# Task_with_ESP32.net
KiCad netlist of a schematic drawn in Altium Designer
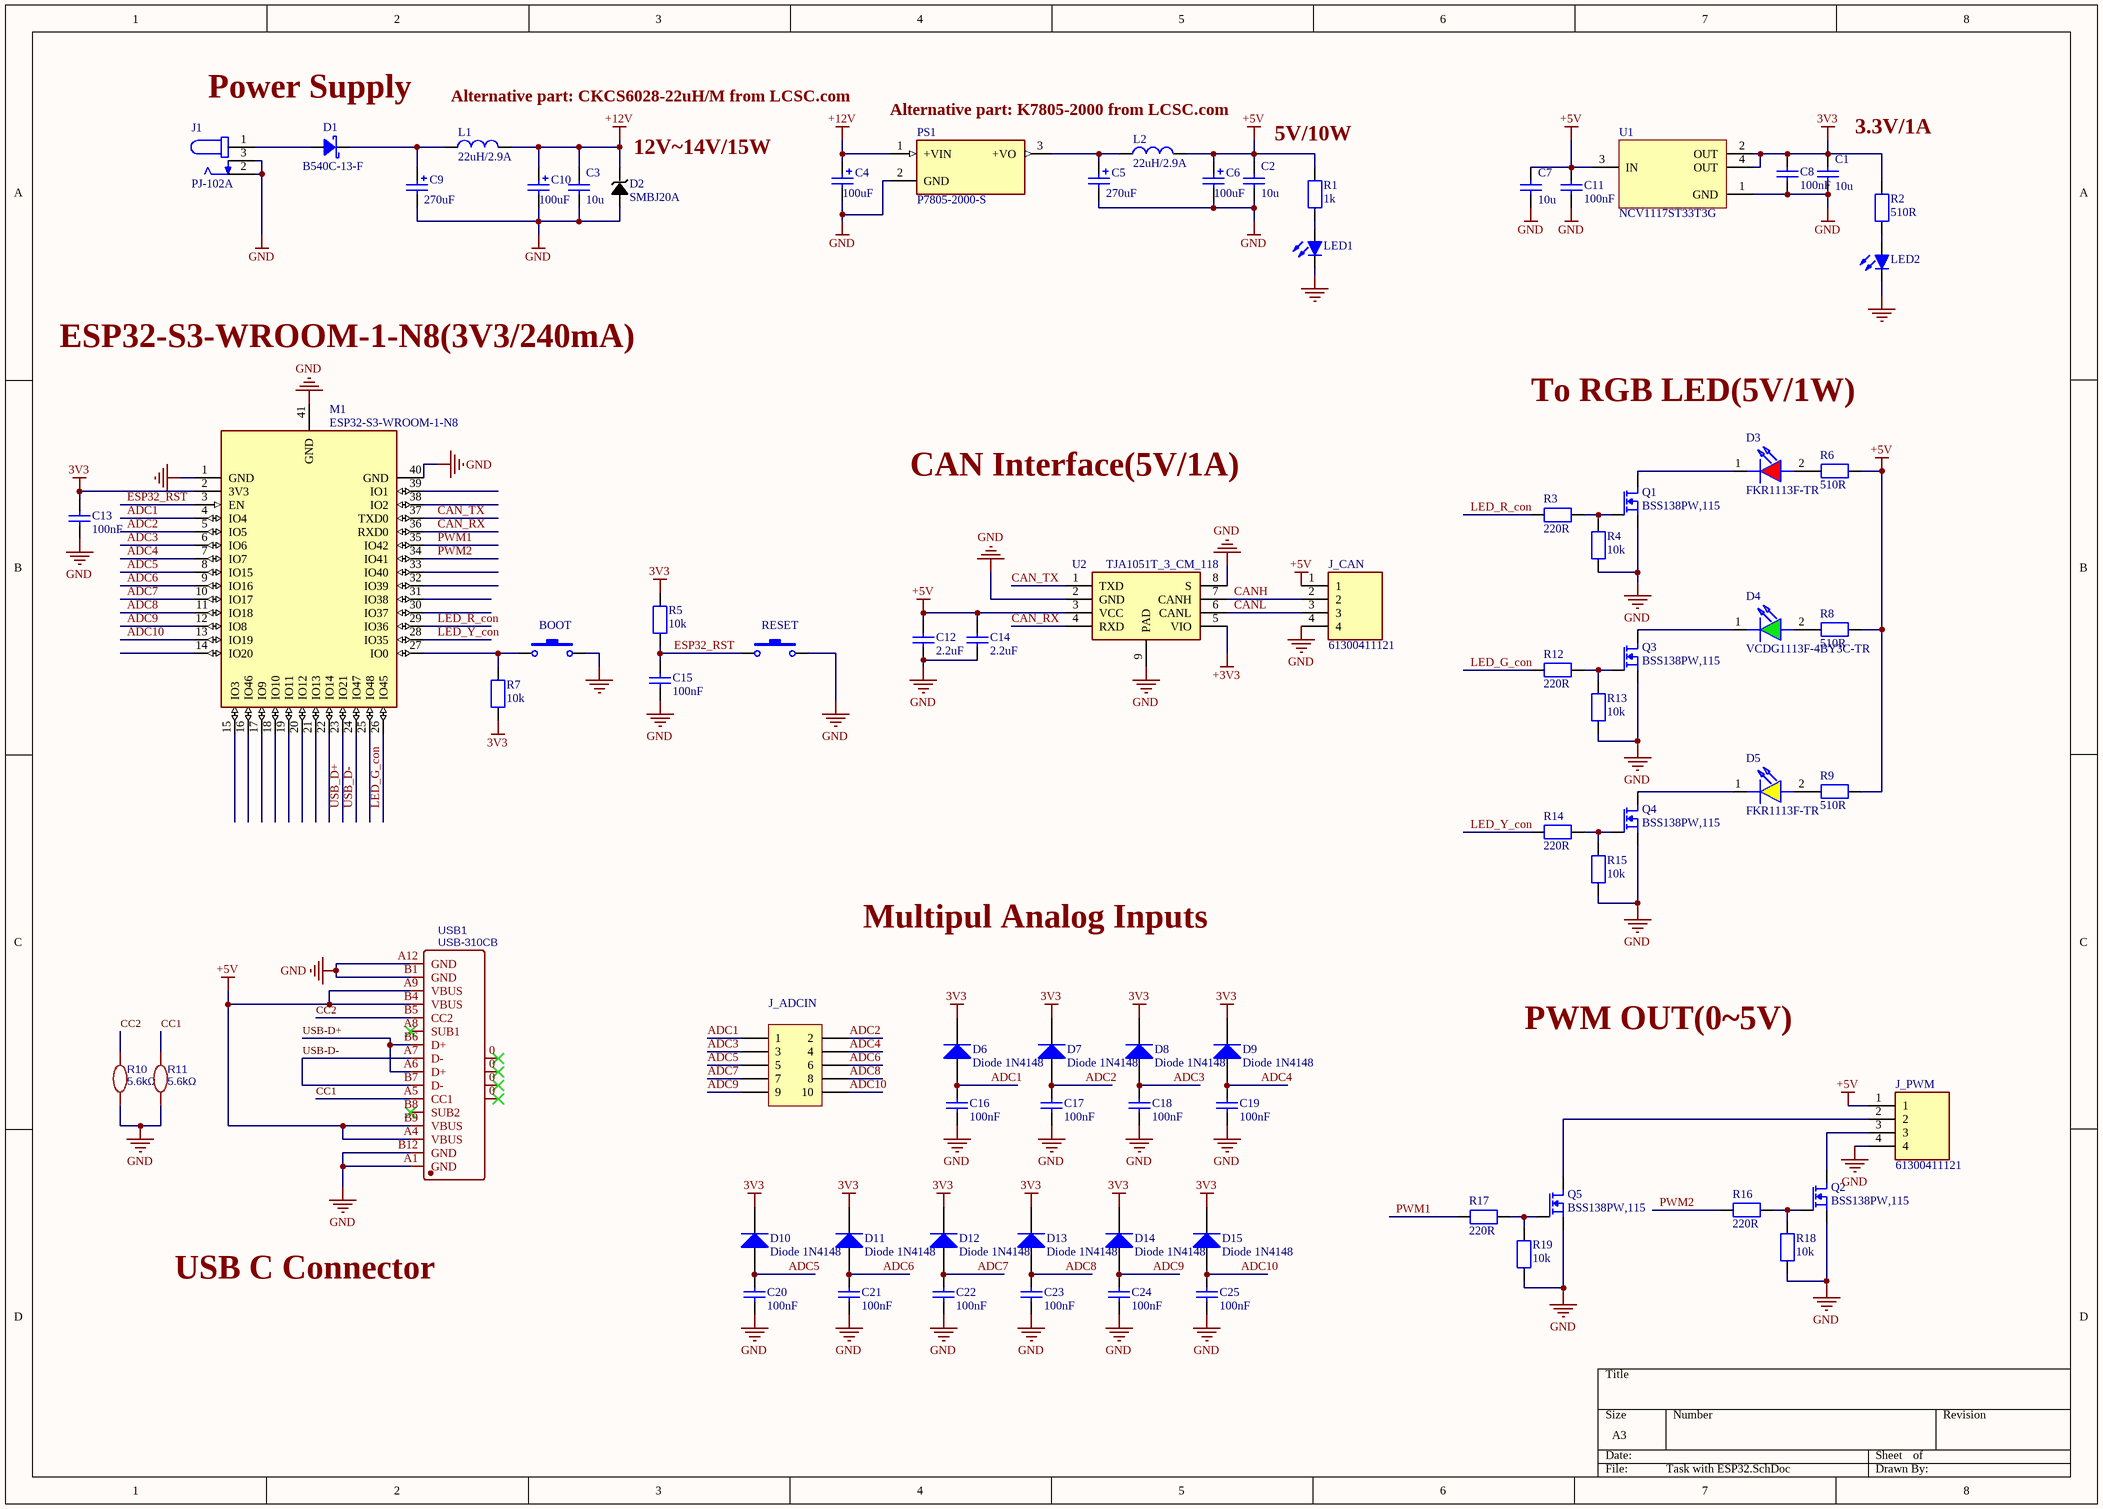
[diagram p0: Task with ESP32.SchDoc]

(export (version "E")
  (design (tool "Eeschema 10.0.6"))
  (components
    (comp (ref "BOOT")
      (value "TL3305BF260QG")
      (footprint "SW_TL3305BF260QG")
      (description "SWITCH TACTILE SPST-NO 0.05A 12V")
      (fields (field (name "MANUFACTURER") "E-Switch"))
      (libsource (lib "Humidity Regulator") (part "TL3305BF260QG"))
    )
    (comp (ref "C1")
      (value "10u")
      (footprint "C1206")
      (description "10uF ± 10% 25V")
      (fields
        (field (name "MANUFACTURER") "Yageo")
        (field (name "MANUFACTURER PART NUMBER") "CC1206KKX7R8BB106")
      )
      (libsource (lib "Humidity Regulator") (part "10uF ± 10% 25V"))
    )
    (comp (ref "C2")
      (value "10u")
      (footprint "C1206")
      (description "10uF ± 10% 25V")
      (fields
        (field (name "MANUFACTURER") "Yageo")
        (field (name "MANUFACTURER PART NUMBER") "CC1206KKX7R8BB106")
      )
      (libsource (lib "Humidity Regulator") (part "10uF ± 10% 25V"))
    )
    (comp (ref "C3")
      (value "10u")
      (footprint "C1206")
      (description "10uF ± 10% 25V")
      (fields
        (field (name "MANUFACTURER") "Yageo")
        (field (name "MANUFACTURER PART NUMBER") "CC1206KKX7R8BB106")
      )
      (libsource (lib "Humidity Regulator") (part "10uF ± 10% 25V"))
    )
    (comp (ref "C4")
      (value "100uF")
      (footprint "CAP_EEUFC1E101S")
      (description "CAP ALUM 100UF 20% 25V SMD")
      (fields
        (field (name "MANUFACTURER PART NUMBER") "EEU-FC1E101S")
        (field (name "MANUFACTURER") "Panasonic")
      )
      (libsource (lib "Humidity Regulator") (part "EEU-FC1E101S"))
    )
    (comp (ref "C5")
      (value "270uF")
      (footprint "CAP_EEU-FK1E271B")
      (description "CAP ALUM 270UF 20% 25V SMD")
      (fields
        (field (name "MANUFACTURER PART NUMBER") "EEU-FC1E271B")
        (field (name "MANUFACTURER") "Panasonic")
      )
      (libsource (lib "Humidity Regulator") (part "EEU-FC1E271B"))
    )
    (comp (ref "C6")
      (value "100uF")
      (footprint "CAP_EEUFC1E101S")
      (description "CAP ALUM 100UF 20% 25V SMD")
      (fields
        (field (name "MANUFACTURER PART NUMBER") "EEU-FC1E101S")
        (field (name "MANUFACTURER") "Panasonic")
      )
      (libsource (lib "Humidity Regulator") (part "EEU-FC1E101S"))
    )
    (comp (ref "C7")
      (value "10u")
      (footprint "C1206")
      (description "10uF ± 10% 25V")
      (fields
        (field (name "MANUFACTURER") "Yageo")
        (field (name "MANUFACTURER PART NUMBER") "CC1206KKX7R8BB106")
      )
      (libsource (lib "Humidity Regulator") (part "10uF ± 10% 25V"))
    )
    (comp (ref "C8")
      (value "100nF")
      (footprint "C0603")
      (description "100nF ± 10% 50V")
      (fields
        (field (name "MANUFACTURER") "Yageo")
        (field (name "MANUFACTURER PART NUMBER") "CC0603KRX7R9BB104")
      )
      (libsource (lib "Humidity Regulator") (part "100nF ± 10% 50V"))
    )
    (comp (ref "C9")
      (value "270uF")
      (footprint "CAP_EEU-FK1E271B")
      (description "CAP ALUM 270UF 20% 25V SMD")
      (fields
        (field (name "MANUFACTURER PART NUMBER") "EEU-FC1E271B")
        (field (name "MANUFACTURER") "Panasonic")
      )
      (libsource (lib "Humidity Regulator") (part "EEU-FC1E271B"))
    )
    (comp (ref "C10")
      (value "100uF")
      (footprint "CAP_EEUFC1E101S")
      (description "CAP ALUM 100UF 20% 25V SMD")
      (fields
        (field (name "MANUFACTURER PART NUMBER") "EEU-FC1E101S")
        (field (name "MANUFACTURER") "Panasonic")
      )
      (libsource (lib "Humidity Regulator") (part "EEU-FC1E101S"))
    )
    (comp (ref "C11")
      (value "100nF")
      (footprint "C0603")
      (description "100nF ± 10% 50V")
      (fields
        (field (name "MANUFACTURER") "Yageo")
        (field (name "MANUFACTURER PART NUMBER") "CC0603KRX7R9BB104")
      )
      (libsource (lib "Humidity Regulator") (part "100nF ± 10% 50V"))
    )
    (comp (ref "C12")
      (value "2.2uF")
      (footprint "C0603")
      (description "2.2uF ± 10% 50V")
      (fields
        (field (name "MANUFACTURER") "Yageo")
        (field (name "MANUFACTURER PART NUMBER") "GRM188R61H225ME11J")
      )
      (libsource (lib "VESC_MotorController") (part "2.2uF ± 10% 50V"))
    )
    (comp (ref "C13")
      (value "100nF")
      (footprint "C0603")
      (description "100nF ± 10% 50V")
      (fields
        (field (name "MANUFACTURER") "Yageo")
        (field (name "MANUFACTURER PART NUMBER") "CC0603KRX7R9BB104")
      )
      (libsource (lib "Humidity Regulator") (part "100nF ± 10% 50V"))
    )
    (comp (ref "C14")
      (value "2.2uF")
      (footprint "C0603")
      (description "2.2uF ± 10% 50V")
      (fields
        (field (name "MANUFACTURER") "Yageo")
        (field (name "MANUFACTURER PART NUMBER") "GRM188R61H225ME11J")
      )
      (libsource (lib "VESC_MotorController") (part "2.2uF ± 10% 50V"))
    )
    (comp (ref "C15")
      (value "100nF")
      (footprint "C0603")
      (description "100nF ± 10% 50V")
      (fields
        (field (name "MANUFACTURER") "Yageo")
        (field (name "MANUFACTURER PART NUMBER") "CC0603KRX7R9BB104")
      )
      (libsource (lib "Humidity Regulator") (part "100nF ± 10% 50V"))
    )
    (comp (ref "C16")
      (value "100nF")
      (footprint "C0402")
      (description "100nF ± 10% 50V")
      (fields
        (field (name "MANUFACTURER") "Yageo")
        (field (name "MANUFACTURER PART NUMBER") "CS0603KRX7R9BB104")
      )
      (libsource (lib "Task with ESP32") (part "100nF ± 10% 50V"))
    )
    (comp (ref "C17")
      (value "100nF")
      (footprint "C0402")
      (description "100nF ± 10% 50V")
      (fields
        (field (name "MANUFACTURER") "Yageo")
        (field (name "MANUFACTURER PART NUMBER") "CS0603KRX7R9BB104")
      )
      (libsource (lib "Task with ESP32") (part "100nF ± 10% 50V"))
    )
    (comp (ref "C18")
      (value "100nF")
      (footprint "C0402")
      (description "100nF ± 10% 50V")
      (fields
        (field (name "MANUFACTURER") "Yageo")
        (field (name "MANUFACTURER PART NUMBER") "CS0603KRX7R9BB104")
      )
      (libsource (lib "Task with ESP32") (part "100nF ± 10% 50V"))
    )
    (comp (ref "C19")
      (value "100nF")
      (footprint "C0402")
      (description "100nF ± 10% 50V")
      (fields
        (field (name "MANUFACTURER") "Yageo")
        (field (name "MANUFACTURER PART NUMBER") "CS0603KRX7R9BB104")
      )
      (libsource (lib "Task with ESP32") (part "100nF ± 10% 50V"))
    )
    (comp (ref "C20")
      (value "100nF")
      (footprint "C0402")
      (description "100nF ± 10% 50V")
      (fields
        (field (name "MANUFACTURER") "Yageo")
        (field (name "MANUFACTURER PART NUMBER") "CS0603KRX7R9BB104")
      )
      (libsource (lib "Task with ESP32") (part "100nF ± 10% 50V"))
    )
    (comp (ref "C21")
      (value "100nF")
      (footprint "C0402")
      (description "100nF ± 10% 50V")
      (fields
        (field (name "MANUFACTURER") "Yageo")
        (field (name "MANUFACTURER PART NUMBER") "CS0603KRX7R9BB104")
      )
      (libsource (lib "Task with ESP32") (part "100nF ± 10% 50V"))
    )
    (comp (ref "C22")
      (value "100nF")
      (footprint "C0402")
      (description "100nF ± 10% 50V")
      (fields
        (field (name "MANUFACTURER") "Yageo")
        (field (name "MANUFACTURER PART NUMBER") "CS0603KRX7R9BB104")
      )
      (libsource (lib "Task with ESP32") (part "100nF ± 10% 50V"))
    )
    (comp (ref "C23")
      (value "100nF")
      (footprint "C0402")
      (description "100nF ± 10% 50V")
      (fields
        (field (name "MANUFACTURER") "Yageo")
        (field (name "MANUFACTURER PART NUMBER") "CS0603KRX7R9BB104")
      )
      (libsource (lib "Task with ESP32") (part "100nF ± 10% 50V"))
    )
    (comp (ref "C24")
      (value "100nF")
      (footprint "C0402")
      (description "100nF ± 10% 50V")
      (fields
        (field (name "MANUFACTURER") "Yageo")
        (field (name "MANUFACTURER PART NUMBER") "CS0603KRX7R9BB104")
      )
      (libsource (lib "Task with ESP32") (part "100nF ± 10% 50V"))
    )
    (comp (ref "C25")
      (value "100nF")
      (footprint "C0402")
      (description "100nF ± 10% 50V")
      (fields
        (field (name "MANUFACTURER") "Yageo")
        (field (name "MANUFACTURER PART NUMBER") "CS0603KRX7R9BB104")
      )
      (libsource (lib "Task with ESP32") (part "100nF ± 10% 50V"))
    )
    (comp (ref "D1")
      (value "B540C-13-F")
      (footprint "DO-214AB2")
      (description "Schottky Diodes & Rectifiers 40V 5A")
      (fields (field (name "MANUFACTURER") "Diodes"))
      (libsource (lib "Humidity Regulator") (part "B540C-13-F"))
    )
    (comp (ref "D2")
      (value "SMBJ20A")
      (footprint "DO-214AA2")
      (description "ESD Suppressors / TVS Diodes 600W, 23.4V, 5%, Unidirectional, TVS")
      (fields (field (name "MANUFACTURER") "Littelfuse"))
      (libsource (lib "Humidity Regulator") (part "ZM4746A-GS08"))
    )
    (comp (ref "D3")
      (value "FKR1113F-TR")
      (footprint "VCDG1113F4BY3CTR")
      (description "R/A LED")
      (fields (field (name "MANUFACTURER") "Stanley Electric"))
      (libsource (lib "Task with ESP32") (part "LED_RED"))
    )
    (comp (ref "D4")
      (value "VCDG1113F-4BY3C-TR")
      (footprint "VCDG1113F4BY3CTR")
      (description "R/A LED")
      (fields (field (name "MANUFACTURER") "Stanley Electric"))
      (libsource (lib "Task with ESP32") (part "LED_GREEN"))
    )
    (comp (ref "D5")
      (value "FKR1113F-TR")
      (footprint "VCDG1113F4BY3CTR")
      (description "R/A LED")
      (fields
        (field (name "MANUFACTURER") "Stanley Electric")
        (field (name "MANUFACTURER PART NUMBER") "FKY1113F-TR")
      )
      (libsource (lib "Task with ESP32") (part "LED_YELLOW"))
    )
    (comp (ref "D6")
      (value "Diode 1N4148")
      (footprint "DO-35")
      (description "High Conductance Fast Diode")
      (fields (field (name "PUBLISHER") "Altium Limited"))
      (libsource (lib "Miscellaneous Devices") (part "Diode 1N4148"))
    )
    (comp (ref "D7")
      (value "Diode 1N4148")
      (footprint "DO-35")
      (description "High Conductance Fast Diode")
      (fields (field (name "PUBLISHER") "Altium Limited"))
      (libsource (lib "Miscellaneous Devices") (part "Diode 1N4148"))
    )
    (comp (ref "D8")
      (value "Diode 1N4148")
      (footprint "DO-35")
      (description "High Conductance Fast Diode")
      (fields (field (name "PUBLISHER") "Altium Limited"))
      (libsource (lib "Miscellaneous Devices") (part "Diode 1N4148"))
    )
    (comp (ref "D9")
      (value "Diode 1N4148")
      (footprint "DO-35")
      (description "High Conductance Fast Diode")
      (fields (field (name "PUBLISHER") "Altium Limited"))
      (libsource (lib "Miscellaneous Devices") (part "Diode 1N4148"))
    )
    (comp (ref "D10")
      (value "Diode 1N4148")
      (footprint "DO-35")
      (description "High Conductance Fast Diode")
      (fields (field (name "PUBLISHER") "Altium Limited"))
      (libsource (lib "Miscellaneous Devices") (part "Diode 1N4148"))
    )
    (comp (ref "D11")
      (value "Diode 1N4148")
      (footprint "DO-35")
      (description "High Conductance Fast Diode")
      (fields (field (name "PUBLISHER") "Altium Limited"))
      (libsource (lib "Miscellaneous Devices") (part "Diode 1N4148"))
    )
    (comp (ref "D12")
      (value "Diode 1N4148")
      (footprint "DO-35")
      (description "High Conductance Fast Diode")
      (fields (field (name "PUBLISHER") "Altium Limited"))
      (libsource (lib "Miscellaneous Devices") (part "Diode 1N4148"))
    )
    (comp (ref "D13")
      (value "Diode 1N4148")
      (footprint "DO-35")
      (description "High Conductance Fast Diode")
      (fields (field (name "PUBLISHER") "Altium Limited"))
      (libsource (lib "Miscellaneous Devices") (part "Diode 1N4148"))
    )
    (comp (ref "D14")
      (value "Diode 1N4148")
      (footprint "DO-35")
      (description "High Conductance Fast Diode")
      (fields (field (name "PUBLISHER") "Altium Limited"))
      (libsource (lib "Miscellaneous Devices") (part "Diode 1N4148"))
    )
    (comp (ref "D15")
      (value "Diode 1N4148")
      (footprint "DO-35")
      (description "High Conductance Fast Diode")
      (fields (field (name "PUBLISHER") "Altium Limited"))
      (libsource (lib "Miscellaneous Devices") (part "Diode 1N4148"))
    )
    (comp (ref "J1")
      (value "PJ-102A")
      (footprint "CUI_PJ-102A")
      (description "CONN PWR JACK 2X5.5MM SOLDER")
      (fields (field (name "MANUFACTURER") "CUI Devices"))
      (libsource (lib "WirelessCharger") (part "PJ-102A"))
    )
    (comp (ref "J_ADCIN")
      (value "~")
      (footprint "HDR2X5H")
      (description "Header, 5-Pin, Dual row, Right Angle")
      (fields (field (name "PUBLISHER") "Altium Limited"))
      (libsource (lib "Miscellaneous Connectors") (part "Header 5X2H"))
    )
    (comp (ref "J_CAN")
      (value "61300411121")
      (footprint "61300411121")
      (description "Headers & Wire Housings WR-PHD 2.54mm Hdr 4P Single Str Gold")
      (fields (field (name "MANUFACTURER") "Wurth Electronic"))
      (libsource (lib "Task with ESP32") (part "Header 4 Pin"))
    )
    (comp (ref "J_PWM")
      (value "61300411121")
      (footprint "61300411121")
      (description "Headers & Wire Housings WR-PHD 2.54mm Hdr 4P Single Str Gold")
      (fields (field (name "MANUFACTURER") "Wurth Electronic"))
      (libsource (lib "Task with ESP32") (part "Header 4 Pin"))
    )
    (comp (ref "L1")
      (value "22uH/2.9A")
      (footprint "IND_SRP6030")
      (description "Power Inductors - SMD Ind,7.1x6.6x2.8mm,22uH+/-20%,2.9A,shd")
      (fields
        (field (name "MANUFACTURER PART NUMBER") "SRP6030WA-220M")
        (field (name "MANUFACTURER") "Bourns")
      )
      (libsource (lib "Humidity Regulator") (part "SRP6030WA-220M"))
    )
    (comp (ref "L2")
      (value "22uH/2.9A")
      (footprint "IND_SRP6030")
      (description "Power Inductors - SMD Ind,7.1x6.6x2.8mm,22uH+/-20%,2.9A,shd")
      (fields
        (field (name "MANUFACTURER PART NUMBER") "SRP6030WA-220M")
        (field (name "MANUFACTURER") "Bourns")
      )
      (libsource (lib "Humidity Regulator") (part "SRP6030WA-220M"))
    )
    (comp (ref "LED1")
      (value "SML-D12U1WT86")
      (footprint "LED0603")
      (description "Typical RED GaAs LED")
      (fields (field (name "MANUFACTURER") "Rohm Semiconductor"))
      (libsource (lib "Humidity Regulator") (part "SML-D12U1WT86"))
    )
    (comp (ref "LED2")
      (value "SML-D12U1WT86")
      (footprint "LED0603")
      (description "Typical RED GaAs LED")
      (fields (field (name "MANUFACTURER") "Rohm Semiconductor"))
      (libsource (lib "Humidity Regulator") (part "SML-D12U1WT86"))
    )
    (comp (ref "M1")
      (value "ESP32-S3-WROOM-1-N8")
      (footprint "ESP32-S3-WROOM-1-N8")
      (description "Bluetooth, WiFi 802.11b/g/n, Bluetooth v5.0 Transceiver Module 2.4GHz PCB Trace Surface Mount")
      (fields (field (name "MANUFACTURER") "Espressif Systems"))
      (libsource (lib "Humidity Regulator") (part "ESP32-S3-WROOM-1-N8"))
    )
    (comp (ref "PS1")
      (value "P7805-2000-S")
      (footprint "CONV_P7805-2000-S")
      (description "2 A Output Current, 6~36 Vdc Input, SIP, Non-Isolated, Dc-Dc Converter")
      (fields (field (name "MANUFACTURER") "CUI Inc."))
      (libsource (lib "P7805-2000-S") (part "P7805-2000-S"))
    )
    (comp (ref "Q1")
      (value "BSS138PW,115")
      (footprint "SOT323-3")
      (description "MOSFET, N CH, 60V, 0.2A")
      (fields (field (name "MANUFACTURER") "Nexperia"))
      (libsource (lib "Humidity Regulator") (part "BSS138PW,115"))
    )
    (comp (ref "Q2")
      (value "BSS138PW,115")
      (footprint "SOT323-3")
      (description "MOSFET, N CH, 60V, 0.2A")
      (fields (field (name "MANUFACTURER") "Nexperia"))
      (libsource (lib "Humidity Regulator") (part "BSS138PW,115"))
    )
    (comp (ref "Q3")
      (value "BSS138PW,115")
      (footprint "SOT323-3")
      (description "MOSFET, N CH, 60V, 0.2A")
      (fields (field (name "MANUFACTURER") "Nexperia"))
      (libsource (lib "Humidity Regulator") (part "BSS138PW,115"))
    )
    (comp (ref "Q4")
      (value "BSS138PW,115")
      (footprint "SOT323-3")
      (description "MOSFET, N CH, 60V, 0.2A")
      (fields (field (name "MANUFACTURER") "Nexperia"))
      (libsource (lib "Humidity Regulator") (part "BSS138PW,115"))
    )
    (comp (ref "Q5")
      (value "BSS138PW,115")
      (footprint "SOT323-3")
      (description "MOSFET, N CH, 60V, 0.2A")
      (fields (field (name "MANUFACTURER") "Nexperia"))
      (libsource (lib "Humidity Regulator") (part "BSS138PW,115"))
    )
    (comp (ref "R1")
      (value "1k")
      (footprint "R0603")
      (description "1 kOhms ±1% 0.1W")
      (fields
        (field (name "MANUFACTURER") "Yageo")
        (field (name "MANUFACTURER PART NUMBER") "RC0603FR-071KL")
      )
      (libsource (lib "Humidity Regulator") (part "1 kOhms ±1% 0.1W"))
    )
    (comp (ref "R2")
      (value "510R")
      (footprint "R0603")
      (description "510 Ohm ±1% 0.1W")
      (fields
        (field (name "MANUFACTURER") "Yageo")
        (field (name "MANUFACTURER PART NUMBER") "RC0603FR-07510RL")
      )
      (libsource (lib "Humidity Regulator") (part "510 Ohm ±1% 0.1W"))
    )
    (comp (ref "R3")
      (value "220R")
      (footprint "R0603")
      (description "220 Ohm ±1% 0.1W")
      (fields
        (field (name "MANUFACTURER") "Yageo")
        (field (name "MANUFACTURER PART NUMBER") "RC0603FR-07220RL")
      )
      (libsource (lib "Humidity Regulator") (part "220 Ohm ±1% 0.1W"))
    )
    (comp (ref "R4")
      (value "10k")
      (footprint "R0603")
      (description "10 kOhms ±1% 0.1W")
      (fields
        (field (name "MANUFACTURER") "Yageo")
        (field (name "MANUFACTURER PART NUMBER") "RC0603FR-0710KL")
      )
      (libsource (lib "Humidity Regulator") (part "10 kOhms ±1% 0.1W"))
    )
    (comp (ref "R5")
      (value "10k")
      (footprint "R0603")
      (description "10 kOhms ±1% 0.1W")
      (fields
        (field (name "MANUFACTURER") "Yageo")
        (field (name "MANUFACTURER PART NUMBER") "RC0603FR-0710KL")
      )
      (libsource (lib "Humidity Regulator") (part "10 kOhms ±1% 0.1W"))
    )
    (comp (ref "R6")
      (value "510R")
      (footprint "R0603")
      (description "510 Ohm ±1% 0.1W")
      (fields
        (field (name "MANUFACTURER") "Yageo")
        (field (name "MANUFACTURER PART NUMBER") "RC0603FR-07510RL")
      )
      (libsource (lib "Humidity Regulator") (part "510 Ohm ±1% 0.1W"))
    )
    (comp (ref "R7")
      (value "10k")
      (footprint "R0603")
      (description "10 kOhms ±1% 0.1W")
      (fields
        (field (name "MANUFACTURER") "Yageo")
        (field (name "MANUFACTURER PART NUMBER") "RC0603FR-0710KL")
      )
      (libsource (lib "Humidity Regulator") (part "10 kOhms ±1% 0.1W"))
    )
    (comp (ref "R8")
      (value "510R")
      (footprint "R0603")
      (description "510 Ohm ±1% 0.1W")
      (fields
        (field (name "MANUFACTURER") "Yageo")
        (field (name "MANUFACTURER PART NUMBER") "RC0603FR-07510RL")
      )
      (libsource (lib "Humidity Regulator") (part "510 Ohm ±1% 0.1W"))
    )
    (comp (ref "R9")
      (value "510R")
      (footprint "R0603")
      (description "510 Ohm ±1% 0.1W")
      (fields
        (field (name "MANUFACTURER") "Yageo")
        (field (name "MANUFACTURER PART NUMBER") "RC0603FR-07510RL")
      )
      (libsource (lib "Humidity Regulator") (part "510 Ohm ±1% 0.1W"))
    )
    (comp (ref "R10")
      (value "5.6kΩ")
      (footprint "R0201")
      (fields
        (field (name "MANUFACTURER") "UNI-ROYAL(Uniroyal Elec)")
        (field (name "MANUFACTURER PART") "NQ01WMJ0562TEE")
        (field (name "CONTRIBUTOR") "LCSC")
      )
      (libsource (lib "altium-import") (part "root_3_5.6kΩ_"))
    )
    (comp (ref "R11")
      (value "5.6kΩ")
      (footprint "R0201")
      (fields
        (field (name "MANUFACTURER") "UNI-ROYAL(Uniroyal Elec)")
        (field (name "MANUFACTURER PART") "NQ01WMJ0562TEE")
        (field (name "CONTRIBUTOR") "LCSC")
      )
      (libsource (lib "altium-import") (part "root_1_5.6kΩ_"))
    )
    (comp (ref "R12")
      (value "220R")
      (footprint "R0603")
      (description "220 Ohm ±1% 0.1W")
      (fields
        (field (name "MANUFACTURER") "Yageo")
        (field (name "MANUFACTURER PART NUMBER") "RC0603FR-07220RL")
      )
      (libsource (lib "Humidity Regulator") (part "220 Ohm ±1% 0.1W"))
    )
    (comp (ref "R13")
      (value "10k")
      (footprint "R0603")
      (description "10 kOhms ±1% 0.1W")
      (fields
        (field (name "MANUFACTURER") "Yageo")
        (field (name "MANUFACTURER PART NUMBER") "RC0603FR-0710KL")
      )
      (libsource (lib "Humidity Regulator") (part "10 kOhms ±1% 0.1W"))
    )
    (comp (ref "R14")
      (value "220R")
      (footprint "R0603")
      (description "220 Ohm ±1% 0.1W")
      (fields
        (field (name "MANUFACTURER") "Yageo")
        (field (name "MANUFACTURER PART NUMBER") "RC0603FR-07220RL")
      )
      (libsource (lib "Humidity Regulator") (part "220 Ohm ±1% 0.1W"))
    )
    (comp (ref "R15")
      (value "10k")
      (footprint "R0603")
      (description "10 kOhms ±1% 0.1W")
      (fields
        (field (name "MANUFACTURER") "Yageo")
        (field (name "MANUFACTURER PART NUMBER") "RC0603FR-0710KL")
      )
      (libsource (lib "Humidity Regulator") (part "10 kOhms ±1% 0.1W"))
    )
    (comp (ref "R16")
      (value "220R")
      (footprint "R0603")
      (description "220 Ohm ±1% 0.1W")
      (fields
        (field (name "MANUFACTURER") "Yageo")
        (field (name "MANUFACTURER PART NUMBER") "RC0603FR-07220RL")
      )
      (libsource (lib "Humidity Regulator") (part "220 Ohm ±1% 0.1W"))
    )
    (comp (ref "R17")
      (value "220R")
      (footprint "R0603")
      (description "220 Ohm ±1% 0.1W")
      (fields
        (field (name "MANUFACTURER") "Yageo")
        (field (name "MANUFACTURER PART NUMBER") "RC0603FR-07220RL")
      )
      (libsource (lib "Humidity Regulator") (part "220 Ohm ±1% 0.1W"))
    )
    (comp (ref "R18")
      (value "10k")
      (footprint "R0603")
      (description "10 kOhms ±1% 0.1W")
      (fields
        (field (name "MANUFACTURER") "Yageo")
        (field (name "MANUFACTURER PART NUMBER") "RC0603FR-0710KL")
      )
      (libsource (lib "Humidity Regulator") (part "10 kOhms ±1% 0.1W"))
    )
    (comp (ref "R19")
      (value "10k")
      (footprint "R0603")
      (description "10 kOhms ±1% 0.1W")
      (fields
        (field (name "MANUFACTURER") "Yageo")
        (field (name "MANUFACTURER PART NUMBER") "RC0603FR-0710KL")
      )
      (libsource (lib "Humidity Regulator") (part "10 kOhms ±1% 0.1W"))
    )
    (comp (ref "RESET")
      (value "TL3305BF260QG")
      (footprint "SW_TL3305BF260QG")
      (description "SWITCH TACTILE SPST-NO 0.05A 12V")
      (fields (field (name "MANUFACTURER") "E-Switch"))
      (libsource (lib "Humidity Regulator") (part "TL3305BF260QG"))
    )
    (comp (ref "U1")
      (value "NCV1117ST33T3G")
      (footprint "SOT223-3")
      (description "LDO Voltage Regulators 3.3V 1.0A Automotive")
      (fields (field (name "MANUFACTURER") "onsemi"))
      (libsource (lib "Humidity Regulator") (part "NCV1117ST33T3G"))
    )
    (comp (ref "U2")
      (value "TJA1051T_3_CM_118")
      (footprint "SOIC127P600X175-8N")
      (description "CAN Interface IC BL Advanced Automotive Analog")
      (fields
        (field (name "MANUFACTURER") "NXP Semiconductors")
        (field (name "MANUFACTURER PART NUMBER") "TJA1051T/3/CM,118")
      )
      (libsource (lib "VESC_MotorController") (part "TJA1051T_3_CM_118"))
    )
    (comp (ref "USB1")
      (value "USB-310CB")
      (footprint "USB-C-SMD_20P-P0.50-L6.5-W11.2")
      (fields (field (name "MANUFACTURER") "HOOYA") (field (name "CONTRIBUTOR") "LCSC"))
      (libsource (lib "altium-import") (part "root_2_USB-310CB_"))
    )
  )
  (nets
    (net (code "1") (name "+3V3") (class "Default")
      (node (ref "U2") (pin "5") (pinfunction "VIO_5") (pintype "passive"))
    )
    (net (code "2") (name "+5V") (class "Default")
      (node (ref "C11") (pin "2") (pinfunction "2_2") (pintype "passive"))
      (node (ref "C12") (pin "2") (pinfunction "2_2") (pintype "passive"))
      (node (ref "C14") (pin "2") (pinfunction "2_2") (pintype "passive"))
      (node (ref "C2") (pin "2") (pinfunction "2_2") (pintype "passive"))
      (node (ref "C6") (pin "1") (pinfunction "1_1") (pintype "passive"))
      (node (ref "C7") (pin "2") (pinfunction "2_2") (pintype "passive"))
      (node (ref "J_CAN") (pin "1") (pinfunction "1_1") (pintype "passive"))
      (node (ref "J_PWM") (pin "1") (pinfunction "1_1") (pintype "passive"))
      (node (ref "L2") (pin "2") (pinfunction "2_2") (pintype "passive"))
      (node (ref "R1") (pin "2") (pinfunction "2_2") (pintype "passive"))
      (node (ref "R6") (pin "1") (pinfunction "1_1") (pintype "passive"))
      (node (ref "R8") (pin "1") (pinfunction "1_1") (pintype "passive"))
      (node (ref "R9") (pin "1") (pinfunction "1_1") (pintype "passive"))
      (node (ref "U1") (pin "3") (pinfunction "IN_3") (pintype "power_in"))
      (node (ref "U2") (pin "3") (pinfunction "VCC_3") (pintype "power_in"))
      (node (ref "USB1") (pin "A4") (pinfunction "VBUS_A4") (pintype "passive"))
      (node (ref "USB1") (pin "A9") (pinfunction "VBUS_A9") (pintype "passive"))
      (node (ref "USB1") (pin "B4") (pinfunction "VBUS_B4") (pintype "passive"))
      (node (ref "USB1") (pin "B9") (pinfunction "VBUS_B9") (pintype "passive"))
    )
    (net (code "3") (name "+12V") (class "Default")
      (node (ref "C10") (pin "1") (pinfunction "1_1") (pintype "passive"))
      (node (ref "C3") (pin "2") (pinfunction "2_2") (pintype "passive"))
      (node (ref "C4") (pin "1") (pinfunction "1_1") (pintype "passive"))
      (node (ref "D2") (pin "C") (pinfunction "C_C") (pintype "passive"))
      (node (ref "L1") (pin "2") (pinfunction "2_2") (pintype "passive"))
      (node (ref "PS1") (pin "1") (pinfunction "+VIN_1") (pintype "input"))
    )
    (net (code "4") (name "/ADC1") (class "Default")
      (node (ref "C16") (pin "2") (pinfunction "2_2") (pintype "passive"))
      (node (ref "D6") (pin "1") (pinfunction "A_1") (pintype "passive"))
      (node (ref "J_ADCIN") (pin "1") (pinfunction "1_1") (pintype "passive"))
      (node (ref "M1") (pin "4") (pinfunction "IO4_4") (pintype "bidirectional"))
    )
    (net (code "5") (name "/ADC2") (class "Default")
      (node (ref "C17") (pin "2") (pinfunction "2_2") (pintype "passive"))
      (node (ref "D7") (pin "1") (pinfunction "A_1") (pintype "passive"))
      (node (ref "J_ADCIN") (pin "2") (pinfunction "2_2") (pintype "passive"))
      (node (ref "M1") (pin "5") (pinfunction "IO5_5") (pintype "bidirectional"))
    )
    (net (code "6") (name "/ADC3") (class "Default")
      (node (ref "C18") (pin "2") (pinfunction "2_2") (pintype "passive"))
      (node (ref "D8") (pin "1") (pinfunction "A_1") (pintype "passive"))
      (node (ref "J_ADCIN") (pin "3") (pinfunction "3_3") (pintype "passive"))
      (node (ref "M1") (pin "6") (pinfunction "IO6_6") (pintype "bidirectional"))
    )
    (net (code "7") (name "/ADC4") (class "Default")
      (node (ref "C19") (pin "2") (pinfunction "2_2") (pintype "passive"))
      (node (ref "D9") (pin "1") (pinfunction "A_1") (pintype "passive"))
      (node (ref "J_ADCIN") (pin "4") (pinfunction "4_4") (pintype "passive"))
      (node (ref "M1") (pin "7") (pinfunction "IO7_7") (pintype "bidirectional"))
    )
    (net (code "8") (name "/ADC5") (class "Default")
      (node (ref "C20") (pin "2") (pinfunction "2_2") (pintype "passive"))
      (node (ref "D10") (pin "1") (pinfunction "A_1") (pintype "passive"))
      (node (ref "J_ADCIN") (pin "5") (pinfunction "5_5") (pintype "passive"))
      (node (ref "M1") (pin "8") (pinfunction "IO15_8") (pintype "bidirectional"))
    )
    (net (code "9") (name "/ADC6") (class "Default")
      (node (ref "C21") (pin "2") (pinfunction "2_2") (pintype "passive"))
      (node (ref "D11") (pin "1") (pinfunction "A_1") (pintype "passive"))
      (node (ref "J_ADCIN") (pin "6") (pinfunction "6_6") (pintype "passive"))
      (node (ref "M1") (pin "9") (pinfunction "IO16_9") (pintype "bidirectional"))
    )
    (net (code "10") (name "/ADC7") (class "Default")
      (node (ref "C22") (pin "2") (pinfunction "2_2") (pintype "passive"))
      (node (ref "D12") (pin "1") (pinfunction "A_1") (pintype "passive"))
      (node (ref "J_ADCIN") (pin "7") (pinfunction "7_7") (pintype "passive"))
      (node (ref "M1") (pin "10") (pinfunction "IO17_10") (pintype "bidirectional"))
    )
    (net (code "11") (name "/ADC8") (class "Default")
      (node (ref "C23") (pin "2") (pinfunction "2_2") (pintype "passive"))
      (node (ref "D13") (pin "1") (pinfunction "A_1") (pintype "passive"))
      (node (ref "J_ADCIN") (pin "8") (pinfunction "8_8") (pintype "passive"))
      (node (ref "M1") (pin "11") (pinfunction "IO18_11") (pintype "bidirectional"))
    )
    (net (code "12") (name "/ADC9") (class "Default")
      (node (ref "C24") (pin "2") (pinfunction "2_2") (pintype "passive"))
      (node (ref "D14") (pin "1") (pinfunction "A_1") (pintype "passive"))
      (node (ref "J_ADCIN") (pin "9") (pinfunction "9_9") (pintype "passive"))
      (node (ref "M1") (pin "12") (pinfunction "IO8_12") (pintype "bidirectional"))
    )
    (net (code "13") (name "/ADC10") (class "Default")
      (node (ref "C25") (pin "2") (pinfunction "2_2") (pintype "passive"))
      (node (ref "D15") (pin "1") (pinfunction "A_1") (pintype "passive"))
      (node (ref "J_ADCIN") (pin "10") (pinfunction "10_10") (pintype "passive"))
      (node (ref "M1") (pin "13") (pinfunction "IO19_13") (pintype "bidirectional"))
    )
    (net (code "14") (name "/CANH") (class "Default")
      (node (ref "J_CAN") (pin "2") (pinfunction "2_2") (pintype "passive"))
      (node (ref "U2") (pin "7") (pinfunction "CANH_7") (pintype "passive"))
    )
    (net (code "15") (name "/CANL") (class "Default")
      (node (ref "J_CAN") (pin "3") (pinfunction "3_3") (pintype "passive"))
      (node (ref "U2") (pin "6") (pinfunction "CANL_6") (pintype "passive"))
    )
    (net (code "16") (name "/CAN_RX") (class "Default")
      (node (ref "M1") (pin "36") (pinfunction "RXD0_36") (pintype "bidirectional"))
      (node (ref "U2") (pin "4") (pinfunction "RXD_4") (pintype "passive"))
    )
    (net (code "17") (name "/CAN_TX") (class "Default")
      (node (ref "M1") (pin "37") (pinfunction "TXD0_37") (pintype "bidirectional"))
      (node (ref "U2") (pin "1") (pinfunction "TXD_1") (pintype "passive"))
    )
    (net (code "18") (name "/CC1") (class "Default")
      (node (ref "R11") (pin "2") (pinfunction "2_2") (pintype "passive"))
      (node (ref "USB1") (pin "A5") (pinfunction "CC1_A5") (pintype "passive"))
    )
    (net (code "19") (name "/CC2") (class "Default")
      (node (ref "R10") (pin "1") (pinfunction "1_1") (pintype "passive"))
      (node (ref "USB1") (pin "B5") (pinfunction "CC2_B5") (pintype "passive"))
    )
    (net (code "20") (name "/ESP32_RST") (class "Default")
      (node (ref "C15") (pin "2") (pinfunction "2_2") (pintype "passive"))
      (node (ref "M1") (pin "3") (pinfunction "EN_3") (pintype "input"))
      (node (ref "R5") (pin "1") (pinfunction "1_1") (pintype "passive"))
      (node (ref "RESET") (pin "1") (pinfunction "1_1") (pintype "passive"))
    )
    (net (code "21") (name "/LED_G_con") (class "Default")
      (node (ref "M1") (pin "26") (pinfunction "IO45_26") (pintype "bidirectional"))
      (node (ref "R12") (pin "1") (pinfunction "1_1") (pintype "passive"))
    )
    (net (code "22") (name "/LED_R_con") (class "Default")
      (node (ref "M1") (pin "29") (pinfunction "IO36_29") (pintype "bidirectional"))
      (node (ref "R3") (pin "1") (pinfunction "1_1") (pintype "passive"))
    )
    (net (code "23") (name "/LED_Y_con") (class "Default")
      (node (ref "M1") (pin "28") (pinfunction "IO35_28") (pintype "bidirectional"))
      (node (ref "R14") (pin "1") (pinfunction "1_1") (pintype "passive"))
    )
    (net (code "24") (name "/PWM1") (class "Default")
      (node (ref "M1") (pin "35") (pinfunction "IO42_35") (pintype "bidirectional"))
      (node (ref "R17") (pin "1") (pinfunction "1_1") (pintype "passive"))
    )
    (net (code "25") (name "/PWM2") (class "Default")
      (node (ref "M1") (pin "34") (pinfunction "IO41_34") (pintype "bidirectional"))
      (node (ref "R16") (pin "1") (pinfunction "1_1") (pintype "passive"))
    )
    (net (code "26") (name "/USB-D+") (class "Default")
      (node (ref "USB1") (pin "A6") (pinfunction "D+_A6") (pintype "passive"))
      (node (ref "USB1") (pin "B6") (pinfunction "D+_B6") (pintype "passive"))
    )
    (net (code "27") (name "/USB-D-") (class "Default")
      (node (ref "USB1") (pin "A7") (pinfunction "D-_A7") (pintype "passive"))
      (node (ref "USB1") (pin "B7") (pinfunction "D-_B7") (pintype "passive"))
    )
    (net (code "28") (name "/USB_D+") (class "Default")
      (node (ref "M1") (pin "23") (pinfunction "IO21_23") (pintype "bidirectional"))
    )
    (net (code "29") (name "/USB_D-") (class "Default")
      (node (ref "M1") (pin "24") (pinfunction "IO47_24") (pintype "bidirectional"))
    )
    (net (code "30") (name "3V3") (class "Default")
      (node (ref "C1") (pin "2") (pinfunction "2_2") (pintype "passive"))
      (node (ref "C13") (pin "2") (pinfunction "2_2") (pintype "passive"))
      (node (ref "C8") (pin "2") (pinfunction "2_2") (pintype "passive"))
      (node (ref "D10") (pin "2") (pinfunction "K_2") (pintype "passive"))
      (node (ref "D11") (pin "2") (pinfunction "K_2") (pintype "passive"))
      (node (ref "D12") (pin "2") (pinfunction "K_2") (pintype "passive"))
      (node (ref "D13") (pin "2") (pinfunction "K_2") (pintype "passive"))
      (node (ref "D14") (pin "2") (pinfunction "K_2") (pintype "passive"))
      (node (ref "D15") (pin "2") (pinfunction "K_2") (pintype "passive"))
      (node (ref "D6") (pin "2") (pinfunction "K_2") (pintype "passive"))
      (node (ref "D7") (pin "2") (pinfunction "K_2") (pintype "passive"))
      (node (ref "D8") (pin "2") (pinfunction "K_2") (pintype "passive"))
      (node (ref "D9") (pin "2") (pinfunction "K_2") (pintype "passive"))
      (node (ref "M1") (pin "2") (pinfunction "3V3_2") (pintype "power_in"))
      (node (ref "R2") (pin "2") (pinfunction "2_2") (pintype "passive"))
      (node (ref "R5") (pin "2") (pinfunction "2_2") (pintype "passive"))
      (node (ref "R7") (pin "2") (pinfunction "2_2") (pintype "passive"))
      (node (ref "U1") (pin "2") (pinfunction "OUT_2") (pintype "power_in"))
      (node (ref "U1") (pin "4") (pinfunction "OUT_4") (pintype "power_in"))
    )
    (net (code "31") (name "GND") (class "Default")
      (node (ref "BOOT") (pin "2") (pinfunction "2_2") (pintype "passive"))
      (node (ref "C1") (pin "1") (pinfunction "1_1") (pintype "passive"))
      (node (ref "C10") (pin "2") (pinfunction "2_2") (pintype "passive"))
      (node (ref "C11") (pin "1") (pinfunction "1_1") (pintype "passive"))
      (node (ref "C12") (pin "1") (pinfunction "1_1") (pintype "passive"))
      (node (ref "C13") (pin "1") (pinfunction "1_1") (pintype "passive"))
      (node (ref "C14") (pin "1") (pinfunction "1_1") (pintype "passive"))
      (node (ref "C15") (pin "1") (pinfunction "1_1") (pintype "passive"))
      (node (ref "C16") (pin "1") (pinfunction "1_1") (pintype "passive"))
      (node (ref "C17") (pin "1") (pinfunction "1_1") (pintype "passive"))
      (node (ref "C18") (pin "1") (pinfunction "1_1") (pintype "passive"))
      (node (ref "C19") (pin "1") (pinfunction "1_1") (pintype "passive"))
      (node (ref "C2") (pin "1") (pinfunction "1_1") (pintype "passive"))
      (node (ref "C20") (pin "1") (pinfunction "1_1") (pintype "passive"))
      (node (ref "C21") (pin "1") (pinfunction "1_1") (pintype "passive"))
      (node (ref "C22") (pin "1") (pinfunction "1_1") (pintype "passive"))
      (node (ref "C23") (pin "1") (pinfunction "1_1") (pintype "passive"))
      (node (ref "C24") (pin "1") (pinfunction "1_1") (pintype "passive"))
      (node (ref "C25") (pin "1") (pinfunction "1_1") (pintype "passive"))
      (node (ref "C3") (pin "1") (pinfunction "1_1") (pintype "passive"))
      (node (ref "C4") (pin "2") (pinfunction "2_2") (pintype "passive"))
      (node (ref "C5") (pin "2") (pinfunction "2_2") (pintype "passive"))
      (node (ref "C6") (pin "2") (pinfunction "2_2") (pintype "passive"))
      (node (ref "C7") (pin "1") (pinfunction "1_1") (pintype "passive"))
      (node (ref "C8") (pin "1") (pinfunction "1_1") (pintype "passive"))
      (node (ref "C9") (pin "2") (pinfunction "2_2") (pintype "passive"))
      (node (ref "D2") (pin "A") (pinfunction "A_A") (pintype "passive"))
      (node (ref "J1") (pin "2") (pinfunction "2_2") (pintype "passive"))
      (node (ref "J1") (pin "3") (pinfunction "3_3") (pintype "passive"))
      (node (ref "J_CAN") (pin "4") (pinfunction "4_4") (pintype "passive"))
      (node (ref "J_PWM") (pin "4") (pinfunction "4_4") (pintype "passive"))
      (node (ref "LED1") (pin "C") (pinfunction "C_C") (pintype "passive"))
      (node (ref "LED2") (pin "C") (pinfunction "C_C") (pintype "passive"))
      (node (ref "M1") (pin "1") (pinfunction "GND_1") (pintype "power_in"))
      (node (ref "M1") (pin "40") (pinfunction "GND_40") (pintype "power_in"))
      (node (ref "M1") (pin "41") (pinfunction "GND_41") (pintype "power_in"))
      (node (ref "PS1") (pin "2") (pinfunction "GND_2") (pintype "power_in"))
      (node (ref "Q1") (pin "2") (pinfunction "S_2") (pintype "passive"))
      (node (ref "Q2") (pin "2") (pinfunction "S_2") (pintype "passive"))
      (node (ref "Q3") (pin "2") (pinfunction "S_2") (pintype "passive"))
      (node (ref "Q4") (pin "2") (pinfunction "S_2") (pintype "passive"))
      (node (ref "Q5") (pin "2") (pinfunction "S_2") (pintype "passive"))
      (node (ref "R10") (pin "2") (pinfunction "2_2") (pintype "passive"))
      (node (ref "R11") (pin "1") (pinfunction "1_1") (pintype "passive"))
      (node (ref "R13") (pin "1") (pinfunction "1_1") (pintype "passive"))
      (node (ref "R15") (pin "1") (pinfunction "1_1") (pintype "passive"))
      (node (ref "R18") (pin "1") (pinfunction "1_1") (pintype "passive"))
      (node (ref "R19") (pin "1") (pinfunction "1_1") (pintype "passive"))
      (node (ref "R4") (pin "1") (pinfunction "1_1") (pintype "passive"))
      (node (ref "RESET") (pin "2") (pinfunction "2_2") (pintype "passive"))
      (node (ref "U1") (pin "1") (pinfunction "GND_1") (pintype "power_in"))
      (node (ref "U2") (pin "2") (pinfunction "GND_2") (pintype "passive"))
      (node (ref "U2") (pin "8") (pinfunction "S_8") (pintype "passive"))
      (node (ref "U2") (pin "9") (pinfunction "PAD_9") (pintype "passive"))
      (node (ref "USB1") (pin "A1") (pinfunction "GND_A1") (pintype "passive"))
      (node (ref "USB1") (pin "A12") (pinfunction "GND_A12") (pintype "passive"))
      (node (ref "USB1") (pin "B1") (pinfunction "GND_B1") (pintype "passive"))
      (node (ref "USB1") (pin "B12") (pinfunction "GND_B12") (pintype "passive"))
    )
    (net (code "32") (name "Net-(C9-Pad1)") (class "Default")
      (node (ref "C9") (pin "1") (pinfunction "1_1") (pintype "passive"))
      (node (ref "D1") (pin "C") (pinfunction "C_C") (pintype "passive"))
      (node (ref "L1") (pin "1") (pinfunction "1_1") (pintype "passive"))
    )
    (net (code "33") (name "Net-(D1-PadA)") (class "Default")
      (node (ref "D1") (pin "A") (pinfunction "A_A") (pintype "passive"))
      (node (ref "J1") (pin "1") (pinfunction "1_1") (pintype "passive"))
    )
    (net (code "34") (name "Net-(D3-A)") (class "Default")
      (node (ref "D3") (pin "2") (pinfunction "A_2") (pintype "passive"))
      (node (ref "R6") (pin "2") (pinfunction "2_2") (pintype "passive"))
    )
    (net (code "35") (name "Net-(D3-K)") (class "Default")
      (node (ref "D3") (pin "1") (pinfunction "K_1") (pintype "passive"))
      (node (ref "Q1") (pin "3") (pinfunction "D_3") (pintype "passive"))
    )
    (net (code "36") (name "Net-(D4-A)") (class "Default")
      (node (ref "D4") (pin "2") (pinfunction "A_2") (pintype "passive"))
      (node (ref "R8") (pin "2") (pinfunction "2_2") (pintype "passive"))
    )
    (net (code "37") (name "Net-(D4-K)") (class "Default")
      (node (ref "D4") (pin "1") (pinfunction "K_1") (pintype "passive"))
      (node (ref "Q3") (pin "3") (pinfunction "D_3") (pintype "passive"))
    )
    (net (code "38") (name "Net-(D5-A)") (class "Default")
      (node (ref "D5") (pin "2") (pinfunction "A_2") (pintype "passive"))
      (node (ref "R9") (pin "2") (pinfunction "2_2") (pintype "passive"))
    )
    (net (code "39") (name "Net-(D5-K)") (class "Default")
      (node (ref "D5") (pin "1") (pinfunction "K_1") (pintype "passive"))
      (node (ref "Q4") (pin "3") (pinfunction "D_3") (pintype "passive"))
    )
    (net (code "40") (name "Net-(LED1-PadA)") (class "Default")
      (node (ref "LED1") (pin "A") (pinfunction "A_A") (pintype "passive"))
      (node (ref "R1") (pin "1") (pinfunction "1_1") (pintype "passive"))
    )
    (net (code "41") (name "Net-(LED2-PadA)") (class "Default")
      (node (ref "LED2") (pin "A") (pinfunction "A_A") (pintype "passive"))
      (node (ref "R2") (pin "1") (pinfunction "1_1") (pintype "passive"))
    )
    (net (code "42") (name "Net-(M1-IO0)") (class "Default")
      (node (ref "BOOT") (pin "1") (pinfunction "1_1") (pintype "passive"))
      (node (ref "M1") (pin "27") (pinfunction "IO0_27") (pintype "bidirectional"))
      (node (ref "R7") (pin "1") (pinfunction "1_1") (pintype "passive"))
    )
    (net (code "43") (name "Net-(PS1-+VO)") (class "Default")
      (node (ref "C5") (pin "1") (pinfunction "1_1") (pintype "passive"))
      (node (ref "L2") (pin "1") (pinfunction "1_1") (pintype "passive"))
      (node (ref "PS1") (pin "3") (pinfunction "+VO_3") (pintype "output"))
    )
    (net (code "44") (name "Net-(Q1-G)") (class "Default")
      (node (ref "Q1") (pin "1") (pinfunction "G_1") (pintype "passive"))
      (node (ref "R3") (pin "2") (pinfunction "2_2") (pintype "passive"))
      (node (ref "R4") (pin "2") (pinfunction "2_2") (pintype "passive"))
    )
    (net (code "45") (name "Net-(Q2-D)") (class "Default")
      (node (ref "J_PWM") (pin "3") (pinfunction "3_3") (pintype "passive"))
      (node (ref "Q2") (pin "3") (pinfunction "D_3") (pintype "passive"))
    )
    (net (code "46") (name "Net-(Q2-G)") (class "Default")
      (node (ref "Q2") (pin "1") (pinfunction "G_1") (pintype "passive"))
      (node (ref "R16") (pin "2") (pinfunction "2_2") (pintype "passive"))
      (node (ref "R18") (pin "2") (pinfunction "2_2") (pintype "passive"))
    )
    (net (code "47") (name "Net-(Q3-G)") (class "Default")
      (node (ref "Q3") (pin "1") (pinfunction "G_1") (pintype "passive"))
      (node (ref "R12") (pin "2") (pinfunction "2_2") (pintype "passive"))
      (node (ref "R13") (pin "2") (pinfunction "2_2") (pintype "passive"))
    )
    (net (code "48") (name "Net-(Q4-G)") (class "Default")
      (node (ref "Q4") (pin "1") (pinfunction "G_1") (pintype "passive"))
      (node (ref "R14") (pin "2") (pinfunction "2_2") (pintype "passive"))
      (node (ref "R15") (pin "2") (pinfunction "2_2") (pintype "passive"))
    )
    (net (code "49") (name "Net-(Q5-D)") (class "Default")
      (node (ref "J_PWM") (pin "2") (pinfunction "2_2") (pintype "passive"))
      (node (ref "Q5") (pin "3") (pinfunction "D_3") (pintype "passive"))
    )
    (net (code "50") (name "Net-(Q5-G)") (class "Default")
      (node (ref "Q5") (pin "1") (pinfunction "G_1") (pintype "passive"))
      (node (ref "R17") (pin "2") (pinfunction "2_2") (pintype "passive"))
      (node (ref "R19") (pin "2") (pinfunction "2_2") (pintype "passive"))
    )
    (net (code "51") (name "unconnected-(M1-IO1-Pad39)") (class "Default")
      (node (ref "M1") (pin "39") (pinfunction "IO1_39") (pintype "bidirectional"))
    )
    (net (code "52") (name "unconnected-(M1-IO2-Pad38)") (class "Default")
      (node (ref "M1") (pin "38") (pinfunction "IO2_38") (pintype "bidirectional"))
    )
    (net (code "53") (name "unconnected-(M1-IO3-Pad15)") (class "Default")
      (node (ref "M1") (pin "15") (pinfunction "IO3_15") (pintype "bidirectional"))
    )
    (net (code "54") (name "unconnected-(M1-IO9-Pad17)") (class "Default")
      (node (ref "M1") (pin "17") (pinfunction "IO9_17") (pintype "bidirectional"))
    )
    (net (code "55") (name "unconnected-(M1-IO10-Pad18)") (class "Default")
      (node (ref "M1") (pin "18") (pinfunction "IO10_18") (pintype "bidirectional"))
    )
    (net (code "56") (name "unconnected-(M1-IO11-Pad19)") (class "Default")
      (node (ref "M1") (pin "19") (pinfunction "IO11_19") (pintype "bidirectional"))
    )
    (net (code "57") (name "unconnected-(M1-IO12-Pad20)") (class "Default")
      (node (ref "M1") (pin "20") (pinfunction "IO12_20") (pintype "bidirectional"))
    )
    (net (code "58") (name "unconnected-(M1-IO13-Pad21)") (class "Default")
      (node (ref "M1") (pin "21") (pinfunction "IO13_21") (pintype "bidirectional"))
    )
    (net (code "59") (name "unconnected-(M1-IO14-Pad22)") (class "Default")
      (node (ref "M1") (pin "22") (pinfunction "IO14_22") (pintype "bidirectional"))
    )
    (net (code "60") (name "unconnected-(M1-IO20-Pad14)") (class "Default")
      (node (ref "M1") (pin "14") (pinfunction "IO20_14") (pintype "bidirectional"))
    )
    (net (code "61") (name "unconnected-(M1-IO37-Pad30)") (class "Default")
      (node (ref "M1") (pin "30") (pinfunction "IO37_30") (pintype "bidirectional"))
    )
    (net (code "62") (name "unconnected-(M1-IO38-Pad31)") (class "Default")
      (node (ref "M1") (pin "31") (pinfunction "IO38_31") (pintype "bidirectional"))
    )
    (net (code "63") (name "unconnected-(M1-IO39-Pad32)") (class "Default")
      (node (ref "M1") (pin "32") (pinfunction "IO39_32") (pintype "bidirectional"))
    )
    (net (code "64") (name "unconnected-(M1-IO40-Pad33)") (class "Default")
      (node (ref "M1") (pin "33") (pinfunction "IO40_33") (pintype "bidirectional"))
    )
    (net (code "65") (name "unconnected-(M1-IO46-Pad16)") (class "Default")
      (node (ref "M1") (pin "16") (pinfunction "IO46_16") (pintype "bidirectional"))
    )
    (net (code "66") (name "unconnected-(M1-IO48-Pad25)") (class "Default")
      (node (ref "M1") (pin "25") (pinfunction "IO48_25") (pintype "bidirectional"))
    )
    (net (code "67") (name "unconnected-(USB1-Pad0)") (class "Default")
      (node (ref "USB1") (pin "0") (pinfunction "0_0") (pintype "passive+no_connect"))
    )
    (net (code "68") (name "unconnected-(USB1-Pad0)_1") (class "Default")
      (node (ref "USB1") (pin "0") (pinfunction "0_0") (pintype "passive+no_connect"))
    )
    (net (code "69") (name "unconnected-(USB1-Pad0)_2") (class "Default")
      (node (ref "USB1") (pin "0") (pinfunction "0_0") (pintype "passive+no_connect"))
    )
    (net (code "70") (name "unconnected-(USB1-Pad0)_3") (class "Default")
      (node (ref "USB1") (pin "0") (pinfunction "0_0") (pintype "passive+no_connect"))
    )
    (net (code "71") (name "unconnected-(USB1-SUB1-PadA8)") (class "Default")
      (node (ref "USB1") (pin "A8") (pinfunction "SUB1_A8") (pintype "passive+no_connect"))
    )
    (net (code "72") (name "unconnected-(USB1-SUB2-PadB8)") (class "Default")
      (node (ref "USB1") (pin "B8") (pinfunction "SUB2_B8") (pintype "passive+no_connect"))
    )
  )
)
